# RoverBaseboard.net
KiCad netlist of a schematic drawn in EAGLE
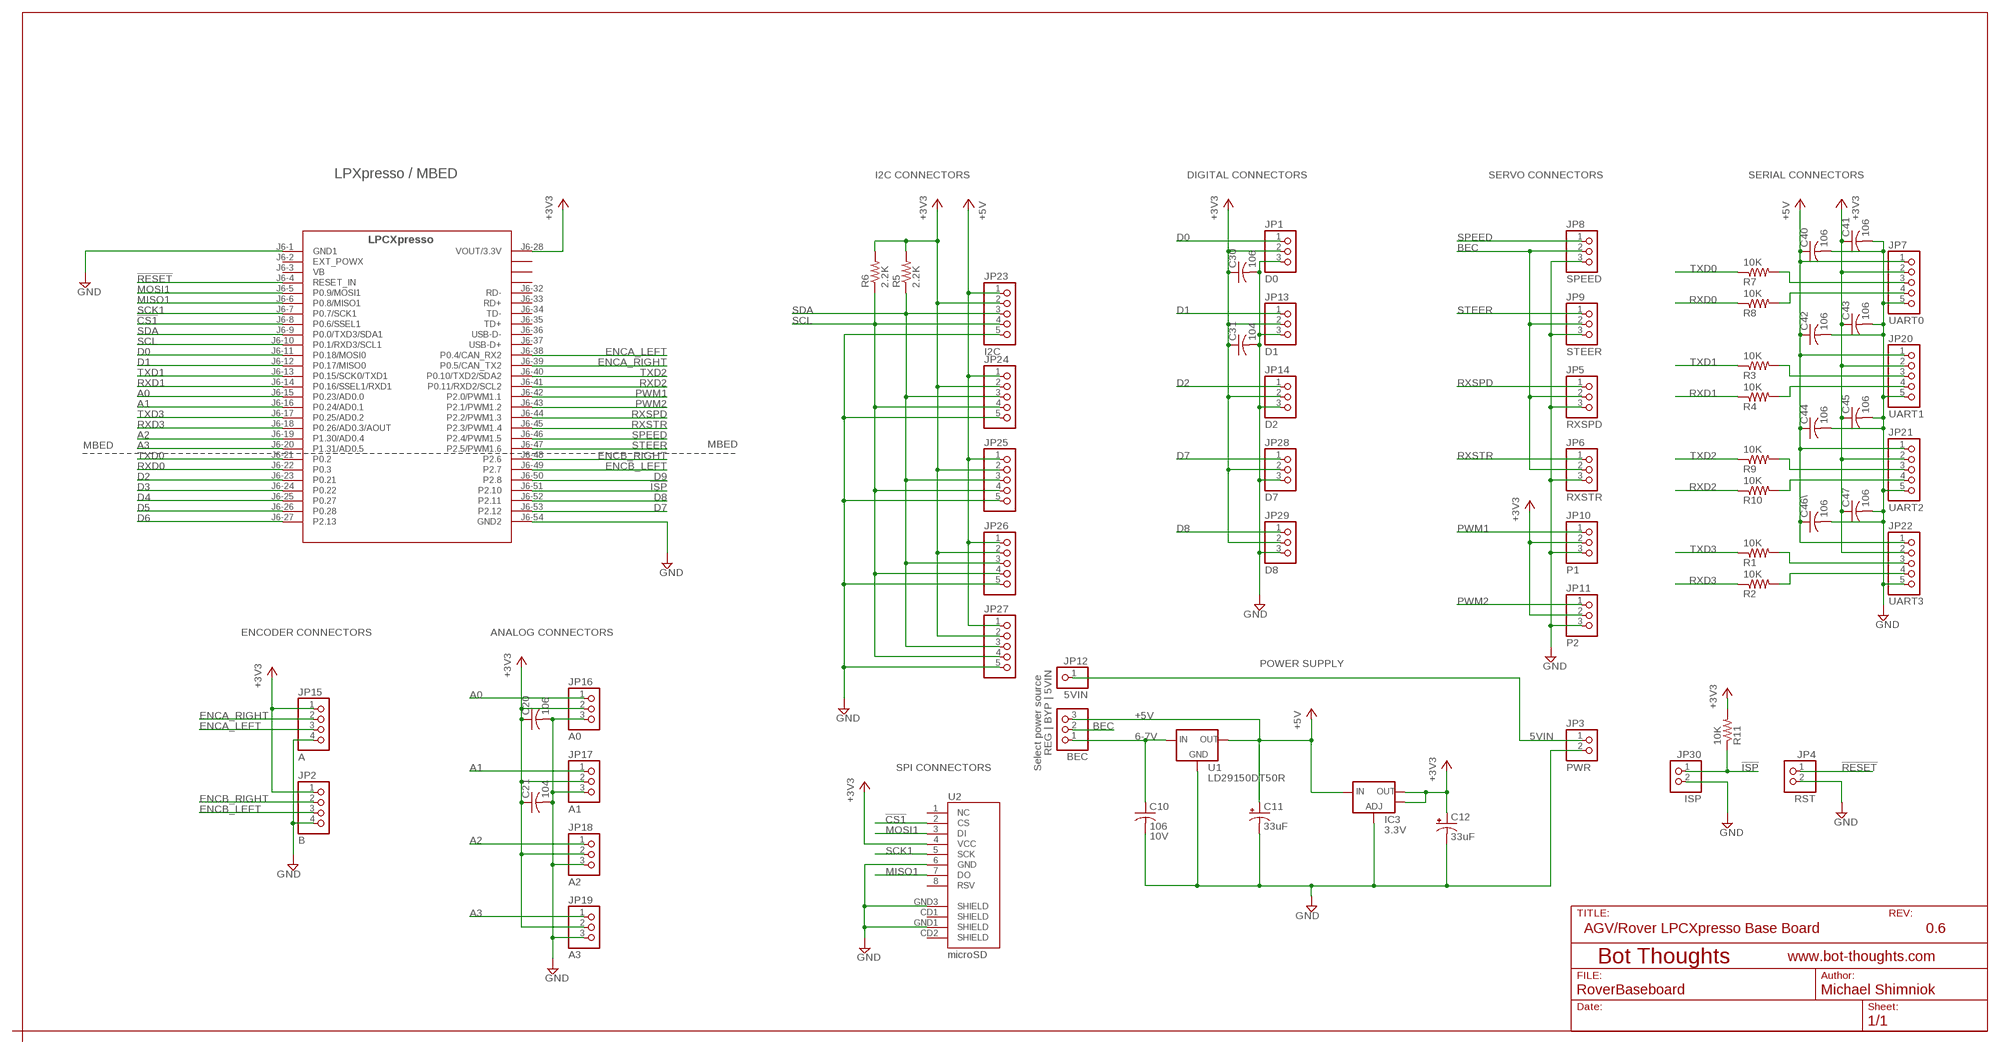
[diagram p0: schematic, sheet 1]

(export (version "E")
  (design (tool "Eeschema 10.0.6"))
  (components
    (comp (ref "BEC")
      (value "REG | BYP | 5VIN")
      (footprint "eagle-import:1X03-S")
      (libsource (lib "eagle-import") (part "PINHD-1X03_2.54-S"))
    )
    (comp (ref "C10")
      (value "106")
      (footprint "eagle-import:C1206")
      (fields (field (name "VOLTAGE") "10V"))
      (libsource (lib "eagle-import") (part "C-USC1206"))
    )
    (comp (ref "C11")
      (value "33uF")
      (footprint "eagle-import:SMC_B")
      (libsource (lib "eagle-import") (part "CPOL-USSMCB"))
    )
    (comp (ref "C12")
      (value "33uF")
      (footprint "eagle-import:SMC_B")
      (libsource (lib "eagle-import") (part "CPOL-USSMCB"))
    )
    (comp (ref "C20")
      (value "106")
      (footprint "eagle-import:C0603")
      (libsource (lib "eagle-import") (part "C-USC0603"))
    )
    (comp (ref "C21")
      (value "104")
      (footprint "eagle-import:C0603")
      (libsource (lib "eagle-import") (part "C-USC0603"))
    )
    (comp (ref "C30")
      (value "106")
      (footprint "eagle-import:C0603")
      (libsource (lib "eagle-import") (part "C-USC0603"))
    )
    (comp (ref "C31")
      (value "104")
      (footprint "eagle-import:C0603")
      (libsource (lib "eagle-import") (part "C-USC0603"))
    )
    (comp (ref "C40")
      (value "106")
      (footprint "eagle-import:C0603")
      (libsource (lib "eagle-import") (part "C-USC0603"))
    )
    (comp (ref "C41")
      (value "106")
      (footprint "eagle-import:C0603")
      (libsource (lib "eagle-import") (part "C-USC0603"))
    )
    (comp (ref "C42")
      (value "106")
      (footprint "eagle-import:C0603")
      (libsource (lib "eagle-import") (part "C-USC0603"))
    )
    (comp (ref "C43")
      (value "106")
      (footprint "eagle-import:C0603")
      (libsource (lib "eagle-import") (part "C-USC0603"))
    )
    (comp (ref "C44")
      (value "106")
      (footprint "eagle-import:C0603")
      (libsource (lib "eagle-import") (part "C-USC0603"))
    )
    (comp (ref "C45")
      (value "106")
      (footprint "eagle-import:C0603")
      (libsource (lib "eagle-import") (part "C-USC0603"))
    )
    (comp (ref "C46\\")
      (value "106")
      (footprint "eagle-import:C0603")
      (libsource (lib "eagle-import") (part "C-USC0603"))
    )
    (comp (ref "C47")
      (value "106")
      (footprint "eagle-import:C0603")
      (libsource (lib "eagle-import") (part "C-USC0603"))
    )
    (comp (ref "IC3")
      (value "3.3V")
      (footprint "eagle-import:SOT223")
      (libsource (lib "eagle-import") (part "V_REG_LM1117SOT223"))
    )
    (comp (ref "JP1")
      (value "D0")
      (footprint "eagle-import:1X03-S")
      (libsource (lib "eagle-import") (part "PINHD-1X03_2.54-S"))
    )
    (comp (ref "JP2")
      (value "B")
      (footprint "eagle-import:1X04-S")
      (libsource (lib "eagle-import") (part "PINHD-1X04_2.54-S"))
    )
    (comp (ref "JP3")
      (value "PWR")
      (footprint "eagle-import:1X02-S")
      (libsource (lib "eagle-import") (part "PINHD-1X02_2.54-S"))
    )
    (comp (ref "JP4")
      (value "RST")
      (footprint "eagle-import:1X02-S")
      (libsource (lib "eagle-import") (part "PINHD-1X02_2.54-S"))
    )
    (comp (ref "JP5")
      (value "RXSPD")
      (footprint "eagle-import:1X03-S")
      (libsource (lib "eagle-import") (part "PINHD-1X03_2.54-S"))
    )
    (comp (ref "JP6")
      (value "RXSTR")
      (footprint "eagle-import:1X03-S")
      (libsource (lib "eagle-import") (part "PINHD-1X03_2.54-S"))
    )
    (comp (ref "JP7")
      (value "UART0")
      (footprint "eagle-import:1X05-S")
      (libsource (lib "eagle-import") (part "PINHD-1X05_2.54-S"))
    )
    (comp (ref "JP8")
      (value "SPEED")
      (footprint "eagle-import:1X03-S")
      (libsource (lib "eagle-import") (part "PINHD-1X03_2.54-S"))
    )
    (comp (ref "JP9")
      (value "STEER")
      (footprint "eagle-import:1X03-S")
      (libsource (lib "eagle-import") (part "PINHD-1X03_2.54-S"))
    )
    (comp (ref "JP10")
      (value "P1")
      (footprint "eagle-import:1X03-S")
      (libsource (lib "eagle-import") (part "PINHD-1X03_2.54-S"))
    )
    (comp (ref "JP11")
      (value "P2")
      (footprint "eagle-import:1X03-S")
      (libsource (lib "eagle-import") (part "PINHD-1X03_2.54-S"))
    )
    (comp (ref "JP12")
      (value "5VIN")
      (footprint "eagle-import:1X01-S")
      (libsource (lib "eagle-import") (part "PINHD-1X01_2.54-S"))
    )
    (comp (ref "JP13")
      (value "D1")
      (footprint "eagle-import:1X03-S")
      (libsource (lib "eagle-import") (part "PINHD-1X03_2.54-S"))
    )
    (comp (ref "JP14")
      (value "D2")
      (footprint "eagle-import:1X03-S")
      (libsource (lib "eagle-import") (part "PINHD-1X03_2.54-S"))
    )
    (comp (ref "JP15")
      (value "A")
      (footprint "eagle-import:1X04-S")
      (libsource (lib "eagle-import") (part "PINHD-1X04_2.54-S"))
    )
    (comp (ref "JP16")
      (value "A0")
      (footprint "eagle-import:1X03-S")
      (libsource (lib "eagle-import") (part "PINHD-1X03_2.54-S"))
    )
    (comp (ref "JP17")
      (value "A1")
      (footprint "eagle-import:1X03-S")
      (libsource (lib "eagle-import") (part "PINHD-1X03_2.54-S"))
    )
    (comp (ref "JP18")
      (value "A2")
      (footprint "eagle-import:1X03-S")
      (libsource (lib "eagle-import") (part "PINHD-1X03_2.54-S"))
    )
    (comp (ref "JP19")
      (value "A3")
      (footprint "eagle-import:1X03-S")
      (libsource (lib "eagle-import") (part "PINHD-1X03_2.54-S"))
    )
    (comp (ref "JP20")
      (value "UART1")
      (footprint "eagle-import:1X05-S")
      (libsource (lib "eagle-import") (part "PINHD-1X05_2.54-S"))
    )
    (comp (ref "JP21")
      (value "UART2")
      (footprint "eagle-import:1X05-S")
      (libsource (lib "eagle-import") (part "PINHD-1X05_2.54-S"))
    )
    (comp (ref "JP22")
      (value "UART3")
      (footprint "eagle-import:1X05-S")
      (libsource (lib "eagle-import") (part "PINHD-1X05_2.54-S"))
    )
    (comp (ref "JP23")
      (value "I2C")
      (footprint "eagle-import:1X05-S")
      (libsource (lib "eagle-import") (part "PINHD-1X05_2.54-S"))
    )
    (comp (ref "JP24")
      (value "PINHD-1X05_2.54-S")
      (footprint "eagle-import:1X05-S")
      (libsource (lib "eagle-import") (part "PINHD-1X05_2.54-S"))
    )
    (comp (ref "JP25")
      (value "PINHD-1X05_2.54-S")
      (footprint "eagle-import:1X05-S")
      (libsource (lib "eagle-import") (part "PINHD-1X05_2.54-S"))
    )
    (comp (ref "JP26")
      (value "PINHD-1X05_2.54-S")
      (footprint "eagle-import:1X05-S")
      (libsource (lib "eagle-import") (part "PINHD-1X05_2.54-S"))
    )
    (comp (ref "JP27")
      (value "PINHD-1X05_2.54-S")
      (footprint "eagle-import:1X05-S")
      (libsource (lib "eagle-import") (part "PINHD-1X05_2.54-S"))
    )
    (comp (ref "JP28")
      (value "D7")
      (footprint "eagle-import:1X03-S")
      (libsource (lib "eagle-import") (part "PINHD-1X03_2.54-S"))
    )
    (comp (ref "JP29")
      (value "D8")
      (footprint "eagle-import:1X03-S")
      (libsource (lib "eagle-import") (part "PINHD-1X03_2.54-S"))
    )
    (comp (ref "JP30")
      (value "ISP")
      (footprint "eagle-import:1X02-S")
      (libsource (lib "eagle-import") (part "PINHD-1X02_2.54-S"))
    )
    (comp (ref "R1")
      (value "10K")
      (footprint "eagle-import:R0603")
      (fields (field (name "MPN") "WCR0805-220RFI"))
      (libsource (lib "eagle-import") (part "R-US_R0603"))
    )
    (comp (ref "R2")
      (value "10K")
      (footprint "eagle-import:R0603")
      (fields (field (name "MPN") "WCR0805-220RFI"))
      (libsource (lib "eagle-import") (part "R-US_R0603"))
    )
    (comp (ref "R3")
      (value "10K")
      (footprint "eagle-import:R0603")
      (fields (field (name "MPN") "WCR0805-220RFI"))
      (libsource (lib "eagle-import") (part "R-US_R0603"))
    )
    (comp (ref "R4")
      (value "10K")
      (footprint "eagle-import:R0603")
      (fields (field (name "MPN") "WCR0805-220RFI"))
      (libsource (lib "eagle-import") (part "R-US_R0603"))
    )
    (comp (ref "R5")
      (value "2.2K")
      (footprint "eagle-import:R0603")
      (libsource (lib "eagle-import") (part "R-US_R0603"))
    )
    (comp (ref "R6")
      (value "2.2K")
      (footprint "eagle-import:R0603")
      (libsource (lib "eagle-import") (part "R-US_R0603"))
    )
    (comp (ref "R7")
      (value "10K")
      (footprint "eagle-import:R0603")
      (fields (field (name "MPN") "WCR0805-220RFI"))
      (libsource (lib "eagle-import") (part "R-US_R0603"))
    )
    (comp (ref "R8")
      (value "10K")
      (footprint "eagle-import:R0603")
      (fields (field (name "MPN") "WCR0805-220RFI"))
      (libsource (lib "eagle-import") (part "R-US_R0603"))
    )
    (comp (ref "R9")
      (value "10K")
      (footprint "eagle-import:R0603")
      (fields (field (name "MPN") "WCR0805-220RFI"))
      (libsource (lib "eagle-import") (part "R-US_R0603"))
    )
    (comp (ref "R10")
      (value "10K")
      (footprint "eagle-import:R0603")
      (fields (field (name "MPN") "WCR0805-220RFI"))
      (libsource (lib "eagle-import") (part "R-US_R0603"))
    )
    (comp (ref "R11")
      (value "10K")
      (footprint "eagle-import:R0603")
      (fields (field (name "MPN") "WCR0805-220RFI"))
      (libsource (lib "eagle-import") (part "R-US_R0603"))
    )
    (comp (ref "U$1")
      (value "LPCXPRESSO")
      (footprint "eagle-import:LPCXPRESSO_NO_PAD")
      (libsource (lib "eagle-import") (part "LPCXPRESSO_NO_PAD_1768_REVB"))
    )
    (comp (ref "U1")
      (value "LD29150DT50R")
      (footprint "eagle-import:DPAK")
      (libsource (lib "eagle-import") (part "LD29150DT"))
    )
    (comp (ref "U2")
      (value "microSD")
      (footprint "eagle-import:MICRO-SD-SOCKET-PP")
      (libsource (lib "eagle-import") (part "USD-SOCKETNEW"))
    )
  )
  (nets
    (net (code "1") (name "+3V3") (class "Default")
      (node (ref "C12") (pin "+") (pinfunction "+_+") (pintype "passive"))
      (node (ref "C20") (pin "1") (pinfunction "1_1") (pintype "passive"))
      (node (ref "C21") (pin "1") (pinfunction "1_1") (pintype "passive"))
      (node (ref "C30") (pin "1") (pinfunction "1_1") (pintype "passive"))
      (node (ref "C31") (pin "1") (pinfunction "1_1") (pintype "passive"))
      (node (ref "C41") (pin "1") (pinfunction "1_1") (pintype "passive"))
      (node (ref "C43") (pin "1") (pinfunction "1_1") (pintype "passive"))
      (node (ref "C45") (pin "1") (pinfunction "1_1") (pintype "passive"))
      (node (ref "C47") (pin "1") (pinfunction "1_1") (pintype "passive"))
      (node (ref "IC3") (pin "2") (pinfunction "OUT_2") (pintype "output"))
      (node (ref "IC3") (pin "4") (pinfunction "OUT_4") (pintype "output"))
      (node (ref "JP1") (pin "2") (pinfunction "2_2") (pintype "passive"))
      (node (ref "JP10") (pin "2") (pinfunction "2_2") (pintype "passive"))
      (node (ref "JP11") (pin "2") (pinfunction "2_2") (pintype "passive"))
      (node (ref "JP13") (pin "2") (pinfunction "2_2") (pintype "passive"))
      (node (ref "JP14") (pin "2") (pinfunction "2_2") (pintype "passive"))
      (node (ref "JP15") (pin "1") (pinfunction "1_1") (pintype "passive"))
      (node (ref "JP16") (pin "2") (pinfunction "2_2") (pintype "passive"))
      (node (ref "JP17") (pin "2") (pinfunction "2_2") (pintype "passive"))
      (node (ref "JP18") (pin "2") (pinfunction "2_2") (pintype "passive"))
      (node (ref "JP19") (pin "2") (pinfunction "2_2") (pintype "passive"))
      (node (ref "JP2") (pin "1") (pinfunction "1_1") (pintype "passive"))
      (node (ref "JP20") (pin "2") (pinfunction "2_2") (pintype "passive"))
      (node (ref "JP21") (pin "2") (pinfunction "2_2") (pintype "passive"))
      (node (ref "JP22") (pin "2") (pinfunction "2_2") (pintype "passive"))
      (node (ref "JP23") (pin "2") (pinfunction "2_2") (pintype "passive"))
      (node (ref "JP24") (pin "2") (pinfunction "2_2") (pintype "passive"))
      (node (ref "JP25") (pin "2") (pinfunction "2_2") (pintype "passive"))
      (node (ref "JP26") (pin "2") (pinfunction "2_2") (pintype "passive"))
      (node (ref "JP27") (pin "2") (pinfunction "2_2") (pintype "passive"))
      (node (ref "JP28") (pin "2") (pinfunction "2_2") (pintype "passive"))
      (node (ref "JP29") (pin "2") (pinfunction "2_2") (pintype "passive"))
      (node (ref "JP7") (pin "2") (pinfunction "2_2") (pintype "passive"))
      (node (ref "R11") (pin "2") (pinfunction "2_2") (pintype "passive"))
      (node (ref "R5") (pin "2") (pinfunction "2_2") (pintype "passive"))
      (node (ref "R6") (pin "2") (pinfunction "2_2") (pintype "passive"))
      (node (ref "U$1") (pin "J6-28") (pinfunction "VOUT/3.3V_J6-28") (pintype "bidirectional"))
      (node (ref "U2") (pin "4") (pinfunction "VCC_4") (pintype "bidirectional"))
    )
    (net (code "2") (name "+5V") (class "Default")
      (node (ref "BEC") (pin "3") (pinfunction "3_3") (pintype "passive"))
      (node (ref "C11") (pin "+") (pinfunction "+_+") (pintype "passive"))
      (node (ref "C40") (pin "1") (pinfunction "1_1") (pintype "passive"))
      (node (ref "C42") (pin "1") (pinfunction "1_1") (pintype "passive"))
      (node (ref "C44") (pin "1") (pinfunction "1_1") (pintype "passive"))
      (node (ref "C46\\") (pin "1") (pinfunction "1_1") (pintype "passive"))
      (node (ref "IC3") (pin "3") (pinfunction "IN_3") (pintype "input"))
      (node (ref "JP20") (pin "1") (pinfunction "1_1") (pintype "passive"))
      (node (ref "JP21") (pin "1") (pinfunction "1_1") (pintype "passive"))
      (node (ref "JP22") (pin "1") (pinfunction "1_1") (pintype "passive"))
      (node (ref "JP23") (pin "1") (pinfunction "1_1") (pintype "passive"))
      (node (ref "JP24") (pin "1") (pinfunction "1_1") (pintype "passive"))
      (node (ref "JP25") (pin "1") (pinfunction "1_1") (pintype "passive"))
      (node (ref "JP26") (pin "1") (pinfunction "1_1") (pintype "passive"))
      (node (ref "JP27") (pin "1") (pinfunction "1_1") (pintype "passive"))
      (node (ref "JP7") (pin "1") (pinfunction "1_1") (pintype "passive"))
      (node (ref "U1") (pin "3") (pinfunction "VOUT_3") (pintype "bidirectional"))
    )
    (net (code "3") (name "/5VIN") (class "Default")
      (node (ref "JP12") (pin "1") (pinfunction "1_1") (pintype "passive"))
      (node (ref "JP3") (pin "1") (pinfunction "1_1") (pintype "passive"))
    )
    (net (code "4") (name "/6-7V") (class "Default")
      (node (ref "BEC") (pin "1") (pinfunction "1_1") (pintype "passive"))
      (node (ref "C10") (pin "1") (pinfunction "1_1") (pintype "passive"))
      (node (ref "U1") (pin "1") (pinfunction "VIN_1") (pintype "bidirectional"))
    )
    (net (code "5") (name "/A0") (class "Default")
      (node (ref "JP16") (pin "1") (pinfunction "1_1") (pintype "passive"))
      (node (ref "U$1") (pin "J6-15") (pinfunction "P0.23/AD0.0_J6-15") (pintype "bidirectional"))
    )
    (net (code "6") (name "/A1") (class "Default")
      (node (ref "JP17") (pin "1") (pinfunction "1_1") (pintype "passive"))
      (node (ref "U$1") (pin "J6-16") (pinfunction "P0.24/AD0.1_J6-16") (pintype "bidirectional"))
    )
    (net (code "7") (name "/A2") (class "Default")
      (node (ref "JP18") (pin "1") (pinfunction "1_1") (pintype "passive"))
      (node (ref "U$1") (pin "J6-19") (pinfunction "P1.30/AD0.4_J6-19") (pintype "bidirectional"))
    )
    (net (code "8") (name "/A3") (class "Default")
      (node (ref "JP19") (pin "1") (pinfunction "1_1") (pintype "passive"))
      (node (ref "U$1") (pin "J6-20") (pinfunction "P1.31/AD0.5_J6-20") (pintype "bidirectional"))
    )
    (net (code "9") (name "/BEC") (class "Default")
      (node (ref "BEC") (pin "2") (pinfunction "2_2") (pintype "passive"))
      (node (ref "JP5") (pin "2") (pinfunction "2_2") (pintype "passive"))
      (node (ref "JP6") (pin "2") (pinfunction "2_2") (pintype "passive"))
      (node (ref "JP8") (pin "2") (pinfunction "2_2") (pintype "passive"))
      (node (ref "JP9") (pin "2") (pinfunction "2_2") (pintype "passive"))
    )
    (net (code "10") (name "/D0") (class "Default")
      (node (ref "JP1") (pin "1") (pinfunction "1_1") (pintype "passive"))
      (node (ref "U$1") (pin "J6-11") (pinfunction "P0.18/MOSI0_J6-11") (pintype "bidirectional"))
    )
    (net (code "11") (name "/D1") (class "Default")
      (node (ref "JP13") (pin "1") (pinfunction "1_1") (pintype "passive"))
      (node (ref "U$1") (pin "J6-12") (pinfunction "P0.17/MISO0_J6-12") (pintype "bidirectional"))
    )
    (net (code "12") (name "/D2") (class "Default")
      (node (ref "JP14") (pin "1") (pinfunction "1_1") (pintype "passive"))
      (node (ref "U$1") (pin "J6-23") (pinfunction "P0.21_J6-23") (pintype "bidirectional"))
    )
    (net (code "13") (name "/D3") (class "Default")
      (node (ref "U$1") (pin "J6-24") (pinfunction "P0.22_J6-24") (pintype "bidirectional"))
    )
    (net (code "14") (name "/D4") (class "Default")
      (node (ref "U$1") (pin "J6-25") (pinfunction "P0.27_J6-25") (pintype "bidirectional"))
    )
    (net (code "15") (name "/D5") (class "Default")
      (node (ref "U$1") (pin "J6-26") (pinfunction "P0.28_J6-26") (pintype "bidirectional"))
    )
    (net (code "16") (name "/D6") (class "Default")
      (node (ref "U$1") (pin "J6-27") (pinfunction "P2.13_J6-27") (pintype "bidirectional"))
    )
    (net (code "17") (name "/D7") (class "Default")
      (node (ref "JP28") (pin "1") (pinfunction "1_1") (pintype "passive"))
      (node (ref "U$1") (pin "J6-53") (pinfunction "P2.12_J6-53") (pintype "bidirectional"))
    )
    (net (code "18") (name "/D8") (class "Default")
      (node (ref "JP29") (pin "1") (pinfunction "1_1") (pintype "passive"))
      (node (ref "U$1") (pin "J6-52") (pinfunction "P2.11_J6-52") (pintype "bidirectional"))
    )
    (net (code "19") (name "/D9") (class "Default")
      (node (ref "U$1") (pin "J6-50") (pinfunction "P2.8_J6-50") (pintype "bidirectional"))
    )
    (net (code "20") (name "/ENCA_LEFT") (class "Default")
      (node (ref "JP15") (pin "3") (pinfunction "3_3") (pintype "passive"))
      (node (ref "U$1") (pin "J6-38") (pinfunction "P0.4/CAN_RX2_J6-38") (pintype "bidirectional"))
    )
    (net (code "21") (name "/ENCA_RIGHT") (class "Default")
      (node (ref "JP15") (pin "2") (pinfunction "2_2") (pintype "passive"))
      (node (ref "U$1") (pin "J6-39") (pinfunction "P0.5/CAN_TX2_J6-39") (pintype "bidirectional"))
    )
    (net (code "22") (name "/ENCB_LEFT") (class "Default")
      (node (ref "JP2") (pin "3") (pinfunction "3_3") (pintype "passive"))
      (node (ref "U$1") (pin "J6-49") (pinfunction "P2.7_J6-49") (pintype "bidirectional"))
    )
    (net (code "23") (name "/ENCB_RIGHT") (class "Default")
      (node (ref "JP2") (pin "2") (pinfunction "2_2") (pintype "passive"))
      (node (ref "U$1") (pin "J6-48") (pinfunction "P2.6_J6-48") (pintype "bidirectional"))
    )
    (net (code "24") (name "/MISO1") (class "Default")
      (node (ref "U$1") (pin "J6-6") (pinfunction "P0.8/MISO1_J6-6") (pintype "bidirectional"))
      (node (ref "U2") (pin "7") (pinfunction "DO_7") (pintype "bidirectional"))
    )
    (net (code "25") (name "/MOSI1") (class "Default")
      (node (ref "U$1") (pin "J6-5") (pinfunction "P0.9/MOSI1_J6-5") (pintype "bidirectional"))
      (node (ref "U2") (pin "3") (pinfunction "DI_3") (pintype "bidirectional"))
    )
    (net (code "26") (name "/PWM1") (class "Default")
      (node (ref "JP10") (pin "1") (pinfunction "1_1") (pintype "passive"))
      (node (ref "U$1") (pin "J6-42") (pinfunction "P2.0/PWM1.1_J6-42") (pintype "bidirectional"))
    )
    (net (code "27") (name "/PWM2") (class "Default")
      (node (ref "JP11") (pin "1") (pinfunction "1_1") (pintype "passive"))
      (node (ref "U$1") (pin "J6-43") (pinfunction "P2.1/PWM1.2_J6-43") (pintype "bidirectional"))
    )
    (net (code "28") (name "/RXD0") (class "Default")
      (node (ref "R8") (pin "1") (pinfunction "1_1") (pintype "passive"))
      (node (ref "U$1") (pin "J6-22") (pinfunction "P0.3_J6-22") (pintype "bidirectional"))
    )
    (net (code "29") (name "/RXD1") (class "Default")
      (node (ref "R4") (pin "1") (pinfunction "1_1") (pintype "passive"))
      (node (ref "U$1") (pin "J6-14") (pinfunction "P0.16/SSEL1/RXD1_J6-14") (pintype "bidirectional"))
    )
    (net (code "30") (name "/RXD2") (class "Default")
      (node (ref "R10") (pin "1") (pinfunction "1_1") (pintype "passive"))
      (node (ref "U$1") (pin "J6-41") (pinfunction "P0.11/RXD2/SCL2_J6-41") (pintype "bidirectional"))
    )
    (net (code "31") (name "/RXD3") (class "Default")
      (node (ref "R2") (pin "1") (pinfunction "1_1") (pintype "passive"))
      (node (ref "U$1") (pin "J6-18") (pinfunction "P0.26/AD0.3/AOUT_J6-18") (pintype "bidirectional"))
    )
    (net (code "32") (name "/RXSPD") (class "Default")
      (node (ref "JP5") (pin "1") (pinfunction "1_1") (pintype "passive"))
      (node (ref "U$1") (pin "J6-44") (pinfunction "P2.2/PWM1.3_J6-44") (pintype "bidirectional"))
    )
    (net (code "33") (name "/RXSTR") (class "Default")
      (node (ref "JP6") (pin "1") (pinfunction "1_1") (pintype "passive"))
      (node (ref "U$1") (pin "J6-45") (pinfunction "P2.3/PWM1.4_J6-45") (pintype "bidirectional"))
    )
    (net (code "34") (name "/SCK1") (class "Default")
      (node (ref "U$1") (pin "J6-7") (pinfunction "P0.7/SCK1_J6-7") (pintype "bidirectional"))
      (node (ref "U2") (pin "5") (pinfunction "SCK_5") (pintype "bidirectional"))
    )
    (net (code "35") (name "/SCL") (class "Default")
      (node (ref "JP23") (pin "4") (pinfunction "4_4") (pintype "passive"))
      (node (ref "JP24") (pin "4") (pinfunction "4_4") (pintype "passive"))
      (node (ref "JP25") (pin "4") (pinfunction "4_4") (pintype "passive"))
      (node (ref "JP26") (pin "4") (pinfunction "4_4") (pintype "passive"))
      (node (ref "JP27") (pin "4") (pinfunction "4_4") (pintype "passive"))
      (node (ref "R6") (pin "1") (pinfunction "1_1") (pintype "passive"))
      (node (ref "U$1") (pin "J6-10") (pinfunction "P0.1/RXD3/SCL1_J6-10") (pintype "bidirectional"))
    )
    (net (code "36") (name "/SDA") (class "Default")
      (node (ref "JP23") (pin "3") (pinfunction "3_3") (pintype "passive"))
      (node (ref "JP24") (pin "3") (pinfunction "3_3") (pintype "passive"))
      (node (ref "JP25") (pin "3") (pinfunction "3_3") (pintype "passive"))
      (node (ref "JP26") (pin "3") (pinfunction "3_3") (pintype "passive"))
      (node (ref "JP27") (pin "3") (pinfunction "3_3") (pintype "passive"))
      (node (ref "R5") (pin "1") (pinfunction "1_1") (pintype "passive"))
      (node (ref "U$1") (pin "J6-9") (pinfunction "P0.0/TXD3/SDA1_J6-9") (pintype "bidirectional"))
    )
    (net (code "37") (name "/SPEED") (class "Default")
      (node (ref "JP8") (pin "1") (pinfunction "1_1") (pintype "passive"))
      (node (ref "U$1") (pin "J6-46") (pinfunction "P2.4/PWM1.5_J6-46") (pintype "bidirectional"))
    )
    (net (code "38") (name "/STEER") (class "Default")
      (node (ref "JP9") (pin "1") (pinfunction "1_1") (pintype "passive"))
      (node (ref "U$1") (pin "J6-47") (pinfunction "P2.5/PWM1.6_J6-47") (pintype "bidirectional"))
    )
    (net (code "39") (name "/TXD0") (class "Default")
      (node (ref "R7") (pin "1") (pinfunction "1_1") (pintype "passive"))
      (node (ref "U$1") (pin "J6-21") (pinfunction "P0.2_J6-21") (pintype "bidirectional"))
    )
    (net (code "40") (name "/TXD1") (class "Default")
      (node (ref "R3") (pin "1") (pinfunction "1_1") (pintype "passive"))
      (node (ref "U$1") (pin "J6-13") (pinfunction "P0.15/SCK0/TXD1_J6-13") (pintype "bidirectional"))
    )
    (net (code "41") (name "/TXD2") (class "Default")
      (node (ref "R9") (pin "1") (pinfunction "1_1") (pintype "passive"))
      (node (ref "U$1") (pin "J6-40") (pinfunction "P0.10/TXD2/SDA2_J6-40") (pintype "bidirectional"))
    )
    (net (code "42") (name "/TXD3") (class "Default")
      (node (ref "R1") (pin "1") (pinfunction "1_1") (pintype "passive"))
      (node (ref "U$1") (pin "J6-17") (pinfunction "P0.25/AD0.2_J6-17") (pintype "bidirectional"))
    )
    (net (code "43") (name "/~{CS1}") (class "Default")
      (node (ref "U$1") (pin "J6-8") (pinfunction "P0.6/SSEL1_J6-8") (pintype "bidirectional"))
      (node (ref "U2") (pin "2") (pinfunction "CS_2") (pintype "bidirectional"))
    )
    (net (code "44") (name "/~{ISP}") (class "Default")
      (node (ref "JP30") (pin "1") (pinfunction "1_1") (pintype "passive"))
      (node (ref "R11") (pin "1") (pinfunction "1_1") (pintype "passive"))
      (node (ref "U$1") (pin "J6-51") (pinfunction "P2.10_J6-51") (pintype "bidirectional"))
    )
    (net (code "45") (name "/~{RESET}") (class "Default")
      (node (ref "JP4") (pin "1") (pinfunction "1_1") (pintype "passive"))
      (node (ref "U$1") (pin "J6-4") (pinfunction "RESET_IN_J6-4") (pintype "bidirectional"))
    )
    (net (code "46") (name "GND") (class "Default")
      (node (ref "C10") (pin "2") (pinfunction "2_2") (pintype "passive"))
      (node (ref "C11") (pin "-") (pinfunction "-_-") (pintype "passive"))
      (node (ref "C12") (pin "-") (pinfunction "-_-") (pintype "passive"))
      (node (ref "C20") (pin "2") (pinfunction "2_2") (pintype "passive"))
      (node (ref "C21") (pin "2") (pinfunction "2_2") (pintype "passive"))
      (node (ref "C30") (pin "2") (pinfunction "2_2") (pintype "passive"))
      (node (ref "C31") (pin "2") (pinfunction "2_2") (pintype "passive"))
      (node (ref "C40") (pin "2") (pinfunction "2_2") (pintype "passive"))
      (node (ref "C41") (pin "2") (pinfunction "2_2") (pintype "passive"))
      (node (ref "C42") (pin "2") (pinfunction "2_2") (pintype "passive"))
      (node (ref "C43") (pin "2") (pinfunction "2_2") (pintype "passive"))
      (node (ref "C44") (pin "2") (pinfunction "2_2") (pintype "passive"))
      (node (ref "C45") (pin "2") (pinfunction "2_2") (pintype "passive"))
      (node (ref "C46\\") (pin "2") (pinfunction "2_2") (pintype "passive"))
      (node (ref "C47") (pin "2") (pinfunction "2_2") (pintype "passive"))
      (node (ref "IC3") (pin "1") (pinfunction "ADJ_1") (pintype "input"))
      (node (ref "JP1") (pin "3") (pinfunction "3_3") (pintype "passive"))
      (node (ref "JP10") (pin "3") (pinfunction "3_3") (pintype "passive"))
      (node (ref "JP11") (pin "3") (pinfunction "3_3") (pintype "passive"))
      (node (ref "JP13") (pin "3") (pinfunction "3_3") (pintype "passive"))
      (node (ref "JP14") (pin "3") (pinfunction "3_3") (pintype "passive"))
      (node (ref "JP15") (pin "4") (pinfunction "4_4") (pintype "passive"))
      (node (ref "JP16") (pin "3") (pinfunction "3_3") (pintype "passive"))
      (node (ref "JP17") (pin "3") (pinfunction "3_3") (pintype "passive"))
      (node (ref "JP18") (pin "3") (pinfunction "3_3") (pintype "passive"))
      (node (ref "JP19") (pin "3") (pinfunction "3_3") (pintype "passive"))
      (node (ref "JP2") (pin "4") (pinfunction "4_4") (pintype "passive"))
      (node (ref "JP20") (pin "5") (pinfunction "5_5") (pintype "passive"))
      (node (ref "JP21") (pin "5") (pinfunction "5_5") (pintype "passive"))
      (node (ref "JP22") (pin "5") (pinfunction "5_5") (pintype "passive"))
      (node (ref "JP23") (pin "5") (pinfunction "5_5") (pintype "passive"))
      (node (ref "JP24") (pin "5") (pinfunction "5_5") (pintype "passive"))
      (node (ref "JP25") (pin "5") (pinfunction "5_5") (pintype "passive"))
      (node (ref "JP26") (pin "5") (pinfunction "5_5") (pintype "passive"))
      (node (ref "JP27") (pin "5") (pinfunction "5_5") (pintype "passive"))
      (node (ref "JP28") (pin "3") (pinfunction "3_3") (pintype "passive"))
      (node (ref "JP29") (pin "3") (pinfunction "3_3") (pintype "passive"))
      (node (ref "JP3") (pin "2") (pinfunction "2_2") (pintype "passive"))
      (node (ref "JP30") (pin "2") (pinfunction "2_2") (pintype "passive"))
      (node (ref "JP4") (pin "2") (pinfunction "2_2") (pintype "passive"))
      (node (ref "JP5") (pin "3") (pinfunction "3_3") (pintype "passive"))
      (node (ref "JP6") (pin "3") (pinfunction "3_3") (pintype "passive"))
      (node (ref "JP7") (pin "5") (pinfunction "5_5") (pintype "passive"))
      (node (ref "JP8") (pin "3") (pinfunction "3_3") (pintype "passive"))
      (node (ref "JP9") (pin "3") (pinfunction "3_3") (pintype "passive"))
      (node (ref "U$1") (pin "J6-1") (pinfunction "GND1_J6-1") (pintype "bidirectional"))
      (node (ref "U$1") (pin "J6-54") (pinfunction "GND2_J6-54") (pintype "bidirectional"))
      (node (ref "U1") (pin "4") (pinfunction "GND_4") (pintype "bidirectional"))
      (node (ref "U2") (pin "6") (pinfunction "GND_6") (pintype "bidirectional"))
      (node (ref "U2") (pin "GND1") (pinfunction "SHIELD_GND1") (pintype "bidirectional"))
      (node (ref "U2") (pin "GND3") (pinfunction "SHIELD_GND3") (pintype "bidirectional"))
    )
    (net (code "47") (name "Net-(JP7-Pad3)") (class "Default")
      (node (ref "JP7") (pin "3") (pinfunction "3_3") (pintype "passive"))
      (node (ref "R7") (pin "2") (pinfunction "2_2") (pintype "passive"))
    )
    (net (code "48") (name "Net-(JP7-Pad4)") (class "Default")
      (node (ref "JP7") (pin "4") (pinfunction "4_4") (pintype "passive"))
      (node (ref "R8") (pin "2") (pinfunction "2_2") (pintype "passive"))
    )
    (net (code "49") (name "Net-(JP20-Pad3)") (class "Default")
      (node (ref "JP20") (pin "3") (pinfunction "3_3") (pintype "passive"))
      (node (ref "R3") (pin "2") (pinfunction "2_2") (pintype "passive"))
    )
    (net (code "50") (name "Net-(JP20-Pad4)") (class "Default")
      (node (ref "JP20") (pin "4") (pinfunction "4_4") (pintype "passive"))
      (node (ref "R4") (pin "2") (pinfunction "2_2") (pintype "passive"))
    )
    (net (code "51") (name "Net-(JP21-Pad3)") (class "Default")
      (node (ref "JP21") (pin "3") (pinfunction "3_3") (pintype "passive"))
      (node (ref "R9") (pin "2") (pinfunction "2_2") (pintype "passive"))
    )
    (net (code "52") (name "Net-(JP21-Pad4)") (class "Default")
      (node (ref "JP21") (pin "4") (pinfunction "4_4") (pintype "passive"))
      (node (ref "R10") (pin "2") (pinfunction "2_2") (pintype "passive"))
    )
    (net (code "53") (name "Net-(JP22-Pad3)") (class "Default")
      (node (ref "JP22") (pin "3") (pinfunction "3_3") (pintype "passive"))
      (node (ref "R1") (pin "2") (pinfunction "2_2") (pintype "passive"))
    )
    (net (code "54") (name "Net-(JP22-Pad4)") (class "Default")
      (node (ref "JP22") (pin "4") (pinfunction "4_4") (pintype "passive"))
      (node (ref "R2") (pin "2") (pinfunction "2_2") (pintype "passive"))
    )
    (net (code "55") (name "unconnected-(U$1-EXT_POWX-PadJ6-2)") (class "Default")
      (node (ref "U$1") (pin "J6-2") (pinfunction "EXT_POWX_J6-2") (pintype "bidirectional"))
    )
    (net (code "56") (name "unconnected-(U$1-P$24-PadJ6-29)") (class "Default")
      (node (ref "U$1") (pin "J6-29") (pinfunction "P$24_J6-29") (pintype "no_connect"))
    )
    (net (code "57") (name "unconnected-(U$1-P$25-PadJ6-30)") (class "Default")
      (node (ref "U$1") (pin "J6-30") (pinfunction "P$25_J6-30") (pintype "no_connect"))
    )
    (net (code "58") (name "unconnected-(U$1-P$26-PadJ6-31)") (class "Default")
      (node (ref "U$1") (pin "J6-31") (pinfunction "P$26_J6-31") (pintype "no_connect"))
    )
    (net (code "59") (name "unconnected-(U$1-RD+-PadJ6-33)") (class "Default")
      (node (ref "U$1") (pin "J6-33") (pinfunction "RD+_J6-33") (pintype "bidirectional"))
    )
    (net (code "60") (name "unconnected-(U$1-RD--PadJ6-32)") (class "Default")
      (node (ref "U$1") (pin "J6-32") (pinfunction "RD-_J6-32") (pintype "bidirectional"))
    )
    (net (code "61") (name "unconnected-(U$1-TD+-PadJ6-35)") (class "Default")
      (node (ref "U$1") (pin "J6-35") (pinfunction "TD+_J6-35") (pintype "bidirectional"))
    )
    (net (code "62") (name "unconnected-(U$1-TD--PadJ6-34)") (class "Default")
      (node (ref "U$1") (pin "J6-34") (pinfunction "TD-_J6-34") (pintype "bidirectional"))
    )
    (net (code "63") (name "unconnected-(U$1-USB-D+-PadJ6-37)") (class "Default")
      (node (ref "U$1") (pin "J6-37") (pinfunction "USB-D+_J6-37") (pintype "bidirectional"))
    )
    (net (code "64") (name "unconnected-(U$1-USB-D--PadJ6-36)") (class "Default")
      (node (ref "U$1") (pin "J6-36") (pinfunction "USB-D-_J6-36") (pintype "bidirectional"))
    )
    (net (code "65") (name "unconnected-(U$1-VB-PadJ6-3)") (class "Default")
      (node (ref "U$1") (pin "J6-3") (pinfunction "VB_J6-3") (pintype "bidirectional"))
    )
    (net (code "66") (name "unconnected-(U2-NC-Pad1)") (class "Default")
      (node (ref "U2") (pin "1") (pinfunction "NC_1") (pintype "bidirectional"))
    )
    (net (code "67") (name "unconnected-(U2-RSV-Pad8)") (class "Default")
      (node (ref "U2") (pin "8") (pinfunction "RSV_8") (pintype "bidirectional"))
    )
    (net (code "68") (name "unconnected-(U2-SHIELD-PadCD1)") (class "Default")
      (node (ref "U2") (pin "CD1") (pinfunction "SHIELD_CD1") (pintype "bidirectional"))
    )
    (net (code "69") (name "unconnected-(U2-SHIELD-PadCD2)") (class "Default")
      (node (ref "U2") (pin "CD2") (pinfunction "SHIELD_CD2") (pintype "bidirectional"))
    )
  )
)
